# MCB_Output_Connectors.net
KiCad netlist of a schematic drawn in Altium Designer
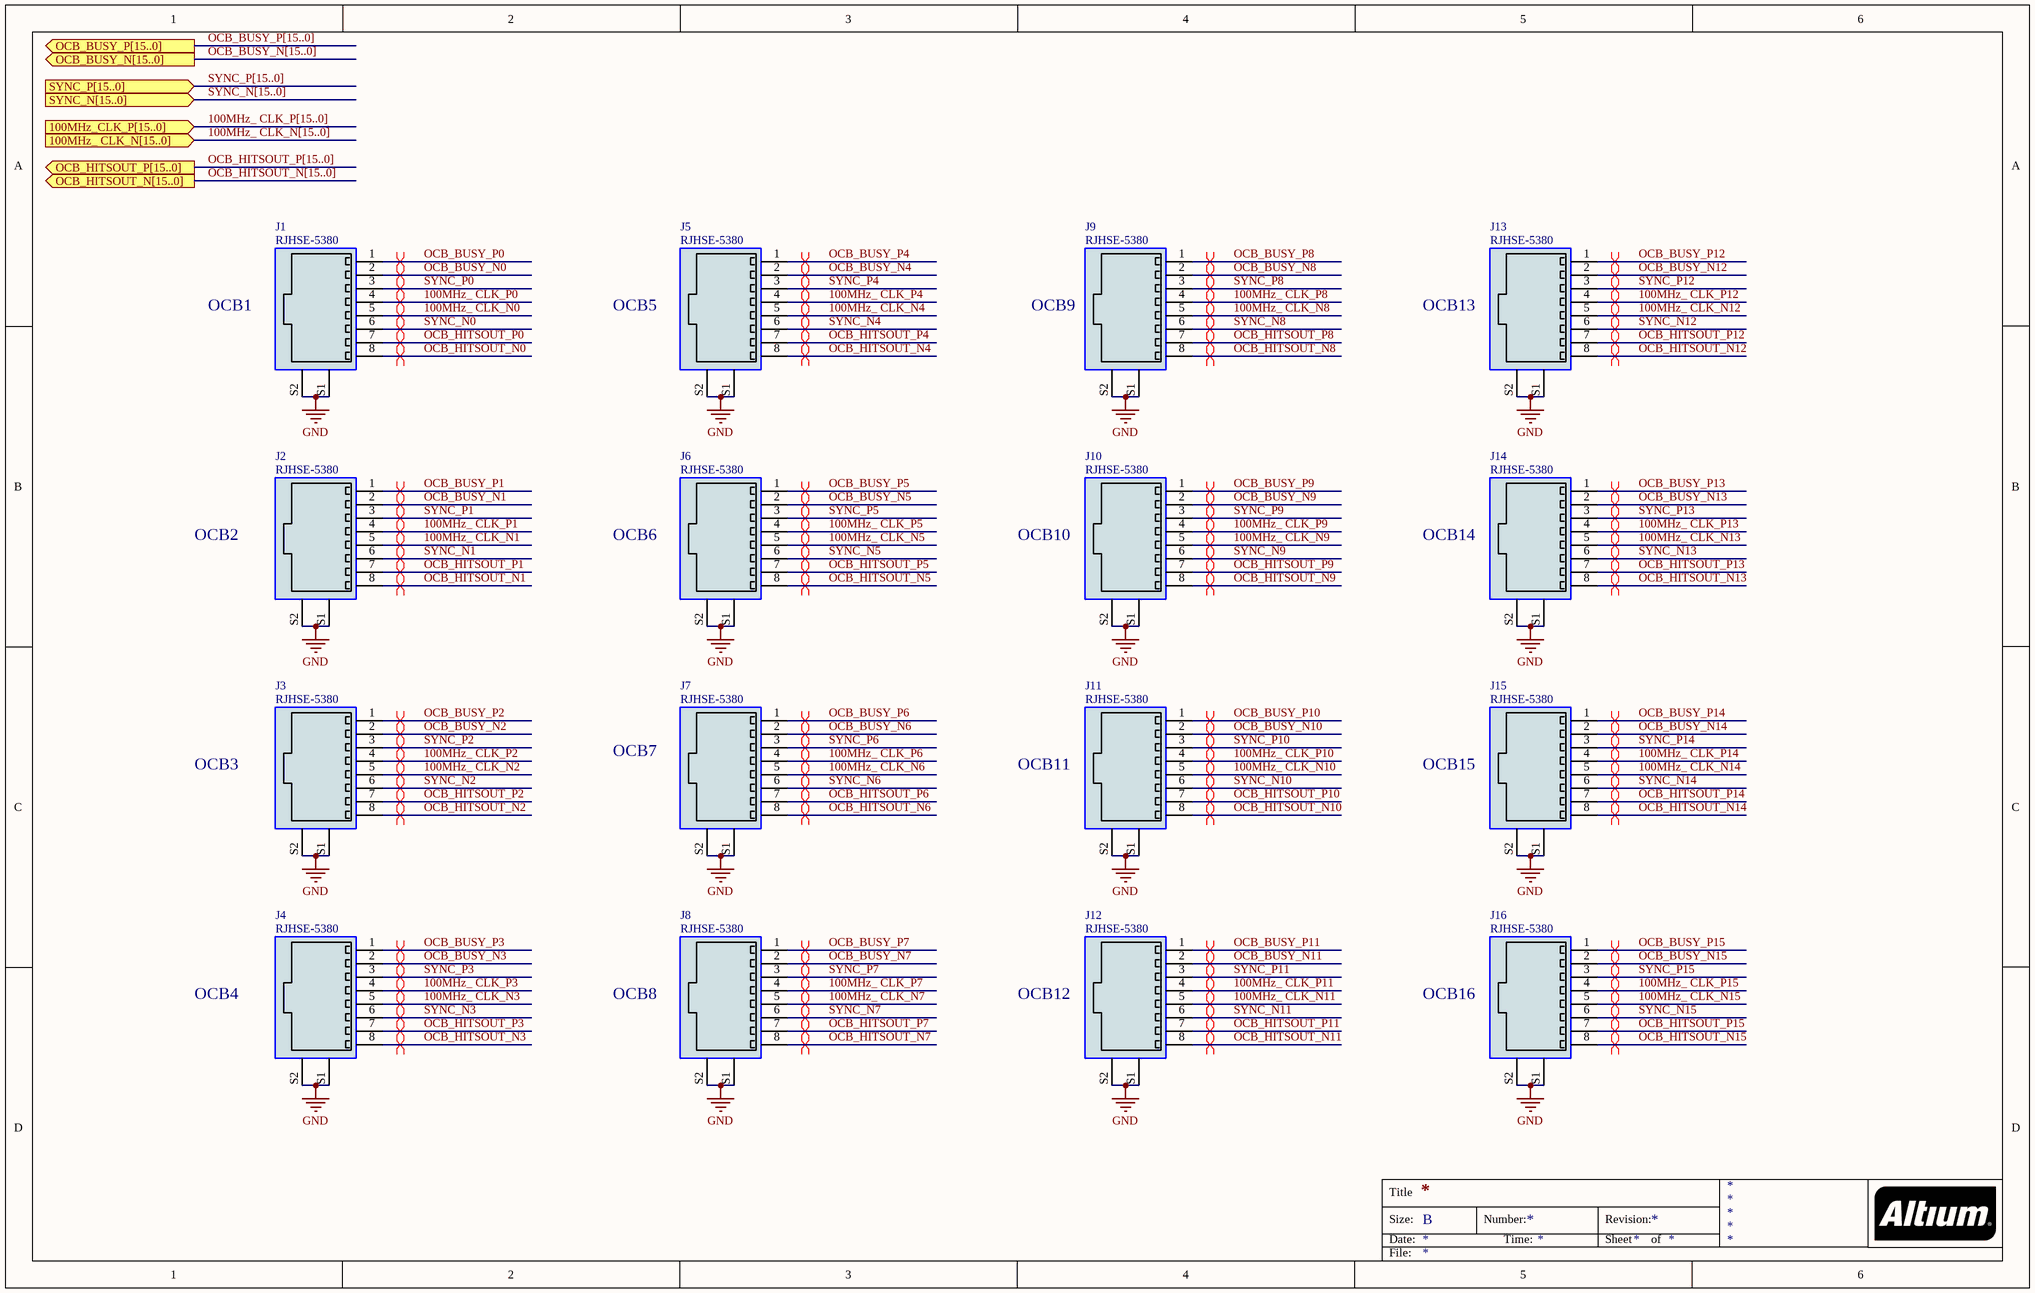
[diagram p0: MCB Output Connectors.SchDoc]

(export (version "E")
  (design (tool "Eeschema 10.0.6"))
  (components
    (comp (ref "J1")
      (value "RJHSE-5380")
      (footprint "RJ45 Right Angle")
      (description "Jack Modular Connector 8p8c (RJ45, Ethernet) 90° Angle (Right) Shielded, EMI Finger -")
      (libsource (lib "MCB") (part "RJHSE-5380"))
    )
    (comp (ref "J2")
      (value "RJHSE-5380")
      (footprint "RJ45 Right Angle")
      (description "Jack Modular Connector 8p8c (RJ45, Ethernet) 90° Angle (Right) Shielded, EMI Finger -")
      (libsource (lib "MCB") (part "RJHSE-5380"))
    )
    (comp (ref "J3")
      (value "RJHSE-5380")
      (footprint "RJ45 Right Angle")
      (description "Jack Modular Connector 8p8c (RJ45, Ethernet) 90° Angle (Right) Shielded, EMI Finger -")
      (libsource (lib "MCB") (part "RJHSE-5380"))
    )
    (comp (ref "J4")
      (value "RJHSE-5380")
      (footprint "RJ45 Right Angle")
      (description "Jack Modular Connector 8p8c (RJ45, Ethernet) 90° Angle (Right) Shielded, EMI Finger -")
      (libsource (lib "MCB") (part "RJHSE-5380"))
    )
    (comp (ref "J5")
      (value "RJHSE-5380")
      (footprint "RJ45 Right Angle")
      (description "Jack Modular Connector 8p8c (RJ45, Ethernet) 90° Angle (Right) Shielded, EMI Finger -")
      (libsource (lib "MCB") (part "RJHSE-5380"))
    )
    (comp (ref "J6")
      (value "RJHSE-5380")
      (footprint "RJ45 Right Angle")
      (description "Jack Modular Connector 8p8c (RJ45, Ethernet) 90° Angle (Right) Shielded, EMI Finger -")
      (libsource (lib "MCB") (part "RJHSE-5380"))
    )
    (comp (ref "J7")
      (value "RJHSE-5380")
      (footprint "RJ45 Right Angle")
      (description "Jack Modular Connector 8p8c (RJ45, Ethernet) 90° Angle (Right) Shielded, EMI Finger -")
      (libsource (lib "MCB") (part "RJHSE-5380"))
    )
    (comp (ref "J8")
      (value "RJHSE-5380")
      (footprint "RJ45 Right Angle")
      (description "Jack Modular Connector 8p8c (RJ45, Ethernet) 90° Angle (Right) Shielded, EMI Finger -")
      (libsource (lib "MCB") (part "RJHSE-5380"))
    )
    (comp (ref "J9")
      (value "RJHSE-5380")
      (footprint "RJ45 Right Angle")
      (description "Jack Modular Connector 8p8c (RJ45, Ethernet) 90° Angle (Right) Shielded, EMI Finger -")
      (libsource (lib "MCB") (part "RJHSE-5380"))
    )
    (comp (ref "J10")
      (value "RJHSE-5380")
      (footprint "RJ45 Right Angle")
      (description "Jack Modular Connector 8p8c (RJ45, Ethernet) 90° Angle (Right) Shielded, EMI Finger -")
      (libsource (lib "MCB") (part "RJHSE-5380"))
    )
    (comp (ref "J11")
      (value "RJHSE-5380")
      (footprint "RJ45 Right Angle")
      (description "Jack Modular Connector 8p8c (RJ45, Ethernet) 90° Angle (Right) Shielded, EMI Finger -")
      (libsource (lib "MCB") (part "RJHSE-5380"))
    )
    (comp (ref "J12")
      (value "RJHSE-5380")
      (footprint "RJ45 Right Angle")
      (description "Jack Modular Connector 8p8c (RJ45, Ethernet) 90° Angle (Right) Shielded, EMI Finger -")
      (libsource (lib "MCB") (part "RJHSE-5380"))
    )
    (comp (ref "J13")
      (value "RJHSE-5380")
      (footprint "RJ45 Right Angle")
      (description "Jack Modular Connector 8p8c (RJ45, Ethernet) 90° Angle (Right) Shielded, EMI Finger -")
      (libsource (lib "MCB") (part "RJHSE-5380"))
    )
    (comp (ref "J14")
      (value "RJHSE-5380")
      (footprint "RJ45 Right Angle")
      (description "Jack Modular Connector 8p8c (RJ45, Ethernet) 90° Angle (Right) Shielded, EMI Finger -")
      (libsource (lib "MCB") (part "RJHSE-5380"))
    )
    (comp (ref "J15")
      (value "RJHSE-5380")
      (footprint "RJ45 Right Angle")
      (description "Jack Modular Connector 8p8c (RJ45, Ethernet) 90° Angle (Right) Shielded, EMI Finger -")
      (libsource (lib "MCB") (part "RJHSE-5380"))
    )
    (comp (ref "J16")
      (value "RJHSE-5380")
      (footprint "RJ45 Right Angle")
      (description "Jack Modular Connector 8p8c (RJ45, Ethernet) 90° Angle (Right) Shielded, EMI Finger -")
      (libsource (lib "MCB") (part "RJHSE-5380"))
    )
  )
  (nets
    (net (code "1") (name "/100MHz_ CLK_N0") (class "Default")
      (node (ref "J1") (pin "5") (pinfunction "5_5") (pintype "passive"))
    )
    (net (code "2") (name "/100MHz_ CLK_N1") (class "Default")
      (node (ref "J2") (pin "5") (pinfunction "5_5") (pintype "passive"))
    )
    (net (code "3") (name "/100MHz_ CLK_N2") (class "Default")
      (node (ref "J3") (pin "5") (pinfunction "5_5") (pintype "passive"))
    )
    (net (code "4") (name "/100MHz_ CLK_N3") (class "Default")
      (node (ref "J4") (pin "5") (pinfunction "5_5") (pintype "passive"))
    )
    (net (code "5") (name "/100MHz_ CLK_N4") (class "Default")
      (node (ref "J5") (pin "5") (pinfunction "5_5") (pintype "passive"))
    )
    (net (code "6") (name "/100MHz_ CLK_N5") (class "Default")
      (node (ref "J6") (pin "5") (pinfunction "5_5") (pintype "passive"))
    )
    (net (code "7") (name "/100MHz_ CLK_N6") (class "Default")
      (node (ref "J7") (pin "5") (pinfunction "5_5") (pintype "passive"))
    )
    (net (code "8") (name "/100MHz_ CLK_N7") (class "Default")
      (node (ref "J8") (pin "5") (pinfunction "5_5") (pintype "passive"))
    )
    (net (code "9") (name "/100MHz_ CLK_N8") (class "Default")
      (node (ref "J9") (pin "5") (pinfunction "5_5") (pintype "passive"))
    )
    (net (code "10") (name "/100MHz_ CLK_N9") (class "Default")
      (node (ref "J10") (pin "5") (pinfunction "5_5") (pintype "passive"))
    )
    (net (code "11") (name "/100MHz_ CLK_N10") (class "Default")
      (node (ref "J11") (pin "5") (pinfunction "5_5") (pintype "passive"))
    )
    (net (code "12") (name "/100MHz_ CLK_N11") (class "Default")
      (node (ref "J12") (pin "5") (pinfunction "5_5") (pintype "passive"))
    )
    (net (code "13") (name "/100MHz_ CLK_N12") (class "Default")
      (node (ref "J13") (pin "5") (pinfunction "5_5") (pintype "passive"))
    )
    (net (code "14") (name "/100MHz_ CLK_N13") (class "Default")
      (node (ref "J14") (pin "5") (pinfunction "5_5") (pintype "passive"))
    )
    (net (code "15") (name "/100MHz_ CLK_N14") (class "Default")
      (node (ref "J15") (pin "5") (pinfunction "5_5") (pintype "passive"))
    )
    (net (code "16") (name "/100MHz_ CLK_N15") (class "Default")
      (node (ref "J16") (pin "5") (pinfunction "5_5") (pintype "passive"))
    )
    (net (code "17") (name "/100MHz_ CLK_P0") (class "Default")
      (node (ref "J1") (pin "4") (pinfunction "4_4") (pintype "passive"))
    )
    (net (code "18") (name "/100MHz_ CLK_P1") (class "Default")
      (node (ref "J2") (pin "4") (pinfunction "4_4") (pintype "passive"))
    )
    (net (code "19") (name "/100MHz_ CLK_P2") (class "Default")
      (node (ref "J3") (pin "4") (pinfunction "4_4") (pintype "passive"))
    )
    (net (code "20") (name "/100MHz_ CLK_P3") (class "Default")
      (node (ref "J4") (pin "4") (pinfunction "4_4") (pintype "passive"))
    )
    (net (code "21") (name "/100MHz_ CLK_P4") (class "Default")
      (node (ref "J5") (pin "4") (pinfunction "4_4") (pintype "passive"))
    )
    (net (code "22") (name "/100MHz_ CLK_P5") (class "Default")
      (node (ref "J6") (pin "4") (pinfunction "4_4") (pintype "passive"))
    )
    (net (code "23") (name "/100MHz_ CLK_P6") (class "Default")
      (node (ref "J7") (pin "4") (pinfunction "4_4") (pintype "passive"))
    )
    (net (code "24") (name "/100MHz_ CLK_P7") (class "Default")
      (node (ref "J8") (pin "4") (pinfunction "4_4") (pintype "passive"))
    )
    (net (code "25") (name "/100MHz_ CLK_P8") (class "Default")
      (node (ref "J9") (pin "4") (pinfunction "4_4") (pintype "passive"))
    )
    (net (code "26") (name "/100MHz_ CLK_P9") (class "Default")
      (node (ref "J10") (pin "4") (pinfunction "4_4") (pintype "passive"))
    )
    (net (code "27") (name "/100MHz_ CLK_P10") (class "Default")
      (node (ref "J11") (pin "4") (pinfunction "4_4") (pintype "passive"))
    )
    (net (code "28") (name "/100MHz_ CLK_P11") (class "Default")
      (node (ref "J12") (pin "4") (pinfunction "4_4") (pintype "passive"))
    )
    (net (code "29") (name "/100MHz_ CLK_P12") (class "Default")
      (node (ref "J13") (pin "4") (pinfunction "4_4") (pintype "passive"))
    )
    (net (code "30") (name "/100MHz_ CLK_P13") (class "Default")
      (node (ref "J14") (pin "4") (pinfunction "4_4") (pintype "passive"))
    )
    (net (code "31") (name "/100MHz_ CLK_P14") (class "Default")
      (node (ref "J15") (pin "4") (pinfunction "4_4") (pintype "passive"))
    )
    (net (code "32") (name "/100MHz_ CLK_P15") (class "Default")
      (node (ref "J16") (pin "4") (pinfunction "4_4") (pintype "passive"))
    )
    (net (code "33") (name "/OCB_BUSY_N0") (class "Default")
      (node (ref "J1") (pin "2") (pinfunction "2_2") (pintype "passive"))
    )
    (net (code "34") (name "/OCB_BUSY_N1") (class "Default")
      (node (ref "J2") (pin "2") (pinfunction "2_2") (pintype "passive"))
    )
    (net (code "35") (name "/OCB_BUSY_N2") (class "Default")
      (node (ref "J3") (pin "2") (pinfunction "2_2") (pintype "passive"))
    )
    (net (code "36") (name "/OCB_BUSY_N3") (class "Default")
      (node (ref "J4") (pin "2") (pinfunction "2_2") (pintype "passive"))
    )
    (net (code "37") (name "/OCB_BUSY_N4") (class "Default")
      (node (ref "J5") (pin "2") (pinfunction "2_2") (pintype "passive"))
    )
    (net (code "38") (name "/OCB_BUSY_N5") (class "Default")
      (node (ref "J6") (pin "2") (pinfunction "2_2") (pintype "passive"))
    )
    (net (code "39") (name "/OCB_BUSY_N6") (class "Default")
      (node (ref "J7") (pin "2") (pinfunction "2_2") (pintype "passive"))
    )
    (net (code "40") (name "/OCB_BUSY_N7") (class "Default")
      (node (ref "J8") (pin "2") (pinfunction "2_2") (pintype "passive"))
    )
    (net (code "41") (name "/OCB_BUSY_N8") (class "Default")
      (node (ref "J9") (pin "2") (pinfunction "2_2") (pintype "passive"))
    )
    (net (code "42") (name "/OCB_BUSY_N9") (class "Default")
      (node (ref "J10") (pin "2") (pinfunction "2_2") (pintype "passive"))
    )
    (net (code "43") (name "/OCB_BUSY_N10") (class "Default")
      (node (ref "J11") (pin "2") (pinfunction "2_2") (pintype "passive"))
    )
    (net (code "44") (name "/OCB_BUSY_N11") (class "Default")
      (node (ref "J12") (pin "2") (pinfunction "2_2") (pintype "passive"))
    )
    (net (code "45") (name "/OCB_BUSY_N12") (class "Default")
      (node (ref "J13") (pin "2") (pinfunction "2_2") (pintype "passive"))
    )
    (net (code "46") (name "/OCB_BUSY_N13") (class "Default")
      (node (ref "J14") (pin "2") (pinfunction "2_2") (pintype "passive"))
    )
    (net (code "47") (name "/OCB_BUSY_N14") (class "Default")
      (node (ref "J15") (pin "2") (pinfunction "2_2") (pintype "passive"))
    )
    (net (code "48") (name "/OCB_BUSY_N15") (class "Default")
      (node (ref "J16") (pin "2") (pinfunction "2_2") (pintype "passive"))
    )
    (net (code "50") (name "/OCB_BUSY_P0") (class "Default")
      (node (ref "J1") (pin "1") (pinfunction "1_1") (pintype "passive"))
    )
    (net (code "51") (name "/OCB_BUSY_P1") (class "Default")
      (node (ref "J2") (pin "1") (pinfunction "1_1") (pintype "passive"))
    )
    (net (code "52") (name "/OCB_BUSY_P2") (class "Default")
      (node (ref "J3") (pin "1") (pinfunction "1_1") (pintype "passive"))
    )
    (net (code "53") (name "/OCB_BUSY_P3") (class "Default")
      (node (ref "J4") (pin "1") (pinfunction "1_1") (pintype "passive"))
    )
    (net (code "54") (name "/OCB_BUSY_P4") (class "Default")
      (node (ref "J5") (pin "1") (pinfunction "1_1") (pintype "passive"))
    )
    (net (code "55") (name "/OCB_BUSY_P5") (class "Default")
      (node (ref "J6") (pin "1") (pinfunction "1_1") (pintype "passive"))
    )
    (net (code "56") (name "/OCB_BUSY_P6") (class "Default")
      (node (ref "J7") (pin "1") (pinfunction "1_1") (pintype "passive"))
    )
    (net (code "57") (name "/OCB_BUSY_P7") (class "Default")
      (node (ref "J8") (pin "1") (pinfunction "1_1") (pintype "passive"))
    )
    (net (code "58") (name "/OCB_BUSY_P8") (class "Default")
      (node (ref "J9") (pin "1") (pinfunction "1_1") (pintype "passive"))
    )
    (net (code "59") (name "/OCB_BUSY_P9") (class "Default")
      (node (ref "J10") (pin "1") (pinfunction "1_1") (pintype "passive"))
    )
    (net (code "60") (name "/OCB_BUSY_P10") (class "Default")
      (node (ref "J11") (pin "1") (pinfunction "1_1") (pintype "passive"))
    )
    (net (code "61") (name "/OCB_BUSY_P11") (class "Default")
      (node (ref "J12") (pin "1") (pinfunction "1_1") (pintype "passive"))
    )
    (net (code "62") (name "/OCB_BUSY_P12") (class "Default")
      (node (ref "J13") (pin "1") (pinfunction "1_1") (pintype "passive"))
    )
    (net (code "63") (name "/OCB_BUSY_P13") (class "Default")
      (node (ref "J14") (pin "1") (pinfunction "1_1") (pintype "passive"))
    )
    (net (code "64") (name "/OCB_BUSY_P14") (class "Default")
      (node (ref "J15") (pin "1") (pinfunction "1_1") (pintype "passive"))
    )
    (net (code "65") (name "/OCB_BUSY_P15") (class "Default")
      (node (ref "J16") (pin "1") (pinfunction "1_1") (pintype "passive"))
    )
    (net (code "67") (name "/OCB_HITSOUT_N0") (class "Default")
      (node (ref "J1") (pin "8") (pinfunction "8_8") (pintype "passive"))
    )
    (net (code "68") (name "/OCB_HITSOUT_N1") (class "Default")
      (node (ref "J2") (pin "8") (pinfunction "8_8") (pintype "passive"))
    )
    (net (code "69") (name "/OCB_HITSOUT_N2") (class "Default")
      (node (ref "J3") (pin "8") (pinfunction "8_8") (pintype "passive"))
    )
    (net (code "70") (name "/OCB_HITSOUT_N3") (class "Default")
      (node (ref "J4") (pin "8") (pinfunction "8_8") (pintype "passive"))
    )
    (net (code "71") (name "/OCB_HITSOUT_N4") (class "Default")
      (node (ref "J5") (pin "8") (pinfunction "8_8") (pintype "passive"))
    )
    (net (code "72") (name "/OCB_HITSOUT_N5") (class "Default")
      (node (ref "J6") (pin "8") (pinfunction "8_8") (pintype "passive"))
    )
    (net (code "73") (name "/OCB_HITSOUT_N6") (class "Default")
      (node (ref "J7") (pin "8") (pinfunction "8_8") (pintype "passive"))
    )
    (net (code "74") (name "/OCB_HITSOUT_N7") (class "Default")
      (node (ref "J8") (pin "8") (pinfunction "8_8") (pintype "passive"))
    )
    (net (code "75") (name "/OCB_HITSOUT_N8") (class "Default")
      (node (ref "J9") (pin "8") (pinfunction "8_8") (pintype "passive"))
    )
    (net (code "76") (name "/OCB_HITSOUT_N9") (class "Default")
      (node (ref "J10") (pin "8") (pinfunction "8_8") (pintype "passive"))
    )
    (net (code "77") (name "/OCB_HITSOUT_N10") (class "Default")
      (node (ref "J11") (pin "8") (pinfunction "8_8") (pintype "passive"))
    )
    (net (code "78") (name "/OCB_HITSOUT_N11") (class "Default")
      (node (ref "J12") (pin "8") (pinfunction "8_8") (pintype "passive"))
    )
    (net (code "79") (name "/OCB_HITSOUT_N12") (class "Default")
      (node (ref "J13") (pin "8") (pinfunction "8_8") (pintype "passive"))
    )
    (net (code "80") (name "/OCB_HITSOUT_N13") (class "Default")
      (node (ref "J14") (pin "8") (pinfunction "8_8") (pintype "passive"))
    )
    (net (code "81") (name "/OCB_HITSOUT_N14") (class "Default")
      (node (ref "J15") (pin "8") (pinfunction "8_8") (pintype "passive"))
    )
    (net (code "82") (name "/OCB_HITSOUT_N15") (class "Default")
      (node (ref "J16") (pin "8") (pinfunction "8_8") (pintype "passive"))
    )
    (net (code "84") (name "/OCB_HITSOUT_P0") (class "Default")
      (node (ref "J1") (pin "7") (pinfunction "7_7") (pintype "passive"))
    )
    (net (code "85") (name "/OCB_HITSOUT_P1") (class "Default")
      (node (ref "J2") (pin "7") (pinfunction "7_7") (pintype "passive"))
    )
    (net (code "86") (name "/OCB_HITSOUT_P2") (class "Default")
      (node (ref "J3") (pin "7") (pinfunction "7_7") (pintype "passive"))
    )
    (net (code "87") (name "/OCB_HITSOUT_P3") (class "Default")
      (node (ref "J4") (pin "7") (pinfunction "7_7") (pintype "passive"))
    )
    (net (code "88") (name "/OCB_HITSOUT_P4") (class "Default")
      (node (ref "J5") (pin "7") (pinfunction "7_7") (pintype "passive"))
    )
    (net (code "89") (name "/OCB_HITSOUT_P5") (class "Default")
      (node (ref "J6") (pin "7") (pinfunction "7_7") (pintype "passive"))
    )
    (net (code "90") (name "/OCB_HITSOUT_P6") (class "Default")
      (node (ref "J7") (pin "7") (pinfunction "7_7") (pintype "passive"))
    )
    (net (code "91") (name "/OCB_HITSOUT_P7") (class "Default")
      (node (ref "J8") (pin "7") (pinfunction "7_7") (pintype "passive"))
    )
    (net (code "92") (name "/OCB_HITSOUT_P8") (class "Default")
      (node (ref "J9") (pin "7") (pinfunction "7_7") (pintype "passive"))
    )
    (net (code "93") (name "/OCB_HITSOUT_P9") (class "Default")
      (node (ref "J10") (pin "7") (pinfunction "7_7") (pintype "passive"))
    )
    (net (code "94") (name "/OCB_HITSOUT_P10") (class "Default")
      (node (ref "J11") (pin "7") (pinfunction "7_7") (pintype "passive"))
    )
    (net (code "95") (name "/OCB_HITSOUT_P11") (class "Default")
      (node (ref "J12") (pin "7") (pinfunction "7_7") (pintype "passive"))
    )
    (net (code "96") (name "/OCB_HITSOUT_P12") (class "Default")
      (node (ref "J13") (pin "7") (pinfunction "7_7") (pintype "passive"))
    )
    (net (code "97") (name "/OCB_HITSOUT_P13") (class "Default")
      (node (ref "J14") (pin "7") (pinfunction "7_7") (pintype "passive"))
    )
    (net (code "98") (name "/OCB_HITSOUT_P14") (class "Default")
      (node (ref "J15") (pin "7") (pinfunction "7_7") (pintype "passive"))
    )
    (net (code "99") (name "/OCB_HITSOUT_P15") (class "Default")
      (node (ref "J16") (pin "7") (pinfunction "7_7") (pintype "passive"))
    )
    (net (code "101") (name "/SYNC_N0") (class "Default")
      (node (ref "J1") (pin "6") (pinfunction "6_6") (pintype "passive"))
    )
    (net (code "102") (name "/SYNC_N1") (class "Default")
      (node (ref "J2") (pin "6") (pinfunction "6_6") (pintype "passive"))
    )
    (net (code "103") (name "/SYNC_N2") (class "Default")
      (node (ref "J3") (pin "6") (pinfunction "6_6") (pintype "passive"))
    )
    (net (code "104") (name "/SYNC_N3") (class "Default")
      (node (ref "J4") (pin "6") (pinfunction "6_6") (pintype "passive"))
    )
    (net (code "105") (name "/SYNC_N4") (class "Default")
      (node (ref "J5") (pin "6") (pinfunction "6_6") (pintype "passive"))
    )
    (net (code "106") (name "/SYNC_N5") (class "Default")
      (node (ref "J6") (pin "6") (pinfunction "6_6") (pintype "passive"))
    )
    (net (code "107") (name "/SYNC_N6") (class "Default")
      (node (ref "J7") (pin "6") (pinfunction "6_6") (pintype "passive"))
    )
    (net (code "108") (name "/SYNC_N7") (class "Default")
      (node (ref "J8") (pin "6") (pinfunction "6_6") (pintype "passive"))
    )
    (net (code "109") (name "/SYNC_N8") (class "Default")
      (node (ref "J9") (pin "6") (pinfunction "6_6") (pintype "passive"))
    )
    (net (code "110") (name "/SYNC_N9") (class "Default")
      (node (ref "J10") (pin "6") (pinfunction "6_6") (pintype "passive"))
    )
    (net (code "111") (name "/SYNC_N10") (class "Default")
      (node (ref "J11") (pin "6") (pinfunction "6_6") (pintype "passive"))
    )
    (net (code "112") (name "/SYNC_N11") (class "Default")
      (node (ref "J12") (pin "6") (pinfunction "6_6") (pintype "passive"))
    )
    (net (code "113") (name "/SYNC_N12") (class "Default")
      (node (ref "J13") (pin "6") (pinfunction "6_6") (pintype "passive"))
    )
    (net (code "114") (name "/SYNC_N13") (class "Default")
      (node (ref "J14") (pin "6") (pinfunction "6_6") (pintype "passive"))
    )
    (net (code "115") (name "/SYNC_N14") (class "Default")
      (node (ref "J15") (pin "6") (pinfunction "6_6") (pintype "passive"))
    )
    (net (code "116") (name "/SYNC_N15") (class "Default")
      (node (ref "J16") (pin "6") (pinfunction "6_6") (pintype "passive"))
    )
    (net (code "118") (name "/SYNC_P0") (class "Default")
      (node (ref "J1") (pin "3") (pinfunction "3_3") (pintype "passive"))
    )
    (net (code "119") (name "/SYNC_P1") (class "Default")
      (node (ref "J2") (pin "3") (pinfunction "3_3") (pintype "passive"))
    )
    (net (code "120") (name "/SYNC_P2") (class "Default")
      (node (ref "J3") (pin "3") (pinfunction "3_3") (pintype "passive"))
    )
    (net (code "121") (name "/SYNC_P3") (class "Default")
      (node (ref "J4") (pin "3") (pinfunction "3_3") (pintype "passive"))
    )
    (net (code "122") (name "/SYNC_P4") (class "Default")
      (node (ref "J5") (pin "3") (pinfunction "3_3") (pintype "passive"))
    )
    (net (code "123") (name "/SYNC_P5") (class "Default")
      (node (ref "J6") (pin "3") (pinfunction "3_3") (pintype "passive"))
    )
    (net (code "124") (name "/SYNC_P6") (class "Default")
      (node (ref "J7") (pin "3") (pinfunction "3_3") (pintype "passive"))
    )
    (net (code "125") (name "/SYNC_P7") (class "Default")
      (node (ref "J8") (pin "3") (pinfunction "3_3") (pintype "passive"))
    )
    (net (code "126") (name "/SYNC_P8") (class "Default")
      (node (ref "J9") (pin "3") (pinfunction "3_3") (pintype "passive"))
    )
    (net (code "127") (name "/SYNC_P9") (class "Default")
      (node (ref "J10") (pin "3") (pinfunction "3_3") (pintype "passive"))
    )
    (net (code "128") (name "/SYNC_P10") (class "Default")
      (node (ref "J11") (pin "3") (pinfunction "3_3") (pintype "passive"))
    )
    (net (code "129") (name "/SYNC_P11") (class "Default")
      (node (ref "J12") (pin "3") (pinfunction "3_3") (pintype "passive"))
    )
    (net (code "130") (name "/SYNC_P12") (class "Default")
      (node (ref "J13") (pin "3") (pinfunction "3_3") (pintype "passive"))
    )
    (net (code "131") (name "/SYNC_P13") (class "Default")
      (node (ref "J14") (pin "3") (pinfunction "3_3") (pintype "passive"))
    )
    (net (code "132") (name "/SYNC_P14") (class "Default")
      (node (ref "J15") (pin "3") (pinfunction "3_3") (pintype "passive"))
    )
    (net (code "133") (name "/SYNC_P15") (class "Default")
      (node (ref "J16") (pin "3") (pinfunction "3_3") (pintype "passive"))
    )
    (net (code "137") (name "GND") (class "Default")
      (node (ref "J1") (pin "S1") (pinfunction "SHIELD_S1") (pintype "passive"))
      (node (ref "J1") (pin "S2") (pinfunction "SHIELD_S2") (pintype "passive"))
      (node (ref "J10") (pin "S1") (pinfunction "SHIELD_S1") (pintype "passive"))
      (node (ref "J10") (pin "S2") (pinfunction "SHIELD_S2") (pintype "passive"))
      (node (ref "J11") (pin "S1") (pinfunction "SHIELD_S1") (pintype "passive"))
      (node (ref "J11") (pin "S2") (pinfunction "SHIELD_S2") (pintype "passive"))
      (node (ref "J12") (pin "S1") (pinfunction "SHIELD_S1") (pintype "passive"))
      (node (ref "J12") (pin "S2") (pinfunction "SHIELD_S2") (pintype "passive"))
      (node (ref "J13") (pin "S1") (pinfunction "SHIELD_S1") (pintype "passive"))
      (node (ref "J13") (pin "S2") (pinfunction "SHIELD_S2") (pintype "passive"))
      (node (ref "J14") (pin "S1") (pinfunction "SHIELD_S1") (pintype "passive"))
      (node (ref "J14") (pin "S2") (pinfunction "SHIELD_S2") (pintype "passive"))
      (node (ref "J15") (pin "S1") (pinfunction "SHIELD_S1") (pintype "passive"))
      (node (ref "J15") (pin "S2") (pinfunction "SHIELD_S2") (pintype "passive"))
      (node (ref "J16") (pin "S1") (pinfunction "SHIELD_S1") (pintype "passive"))
      (node (ref "J16") (pin "S2") (pinfunction "SHIELD_S2") (pintype "passive"))
      (node (ref "J2") (pin "S1") (pinfunction "SHIELD_S1") (pintype "passive"))
      (node (ref "J2") (pin "S2") (pinfunction "SHIELD_S2") (pintype "passive"))
      (node (ref "J3") (pin "S1") (pinfunction "SHIELD_S1") (pintype "passive"))
      (node (ref "J3") (pin "S2") (pinfunction "SHIELD_S2") (pintype "passive"))
      (node (ref "J4") (pin "S1") (pinfunction "SHIELD_S1") (pintype "passive"))
      (node (ref "J4") (pin "S2") (pinfunction "SHIELD_S2") (pintype "passive"))
      (node (ref "J5") (pin "S1") (pinfunction "SHIELD_S1") (pintype "passive"))
      (node (ref "J5") (pin "S2") (pinfunction "SHIELD_S2") (pintype "passive"))
      (node (ref "J6") (pin "S1") (pinfunction "SHIELD_S1") (pintype "passive"))
      (node (ref "J6") (pin "S2") (pinfunction "SHIELD_S2") (pintype "passive"))
      (node (ref "J7") (pin "S1") (pinfunction "SHIELD_S1") (pintype "passive"))
      (node (ref "J7") (pin "S2") (pinfunction "SHIELD_S2") (pintype "passive"))
      (node (ref "J8") (pin "S1") (pinfunction "SHIELD_S1") (pintype "passive"))
      (node (ref "J8") (pin "S2") (pinfunction "SHIELD_S2") (pintype "passive"))
      (node (ref "J9") (pin "S1") (pinfunction "SHIELD_S1") (pintype "passive"))
      (node (ref "J9") (pin "S2") (pinfunction "SHIELD_S2") (pintype "passive"))
    )
    (net (code "138") (name "unconnected-(J1-Pad9)") (class "Default")
      (node (ref "J1") (pin "9") (pinfunction "9_9") (pintype "passive"))
    )
    (net (code "139") (name "unconnected-(J1-Pad10)") (class "Default")
      (node (ref "J1") (pin "10") (pinfunction "10_10") (pintype "passive"))
    )
    (net (code "140") (name "unconnected-(J1-Pad11)") (class "Default")
      (node (ref "J1") (pin "11") (pinfunction "11_11") (pintype "passive"))
    )
    (net (code "141") (name "unconnected-(J1-Pad12)") (class "Default")
      (node (ref "J1") (pin "12") (pinfunction "12_12") (pintype "passive"))
    )
    (net (code "142") (name "unconnected-(J2-Pad9)") (class "Default")
      (node (ref "J2") (pin "9") (pinfunction "9_9") (pintype "passive"))
    )
    (net (code "143") (name "unconnected-(J2-Pad10)") (class "Default")
      (node (ref "J2") (pin "10") (pinfunction "10_10") (pintype "passive"))
    )
    (net (code "144") (name "unconnected-(J2-Pad11)") (class "Default")
      (node (ref "J2") (pin "11") (pinfunction "11_11") (pintype "passive"))
    )
    (net (code "145") (name "unconnected-(J2-Pad12)") (class "Default")
      (node (ref "J2") (pin "12") (pinfunction "12_12") (pintype "passive"))
    )
    (net (code "146") (name "unconnected-(J3-Pad9)") (class "Default")
      (node (ref "J3") (pin "9") (pinfunction "9_9") (pintype "passive"))
    )
    (net (code "147") (name "unconnected-(J3-Pad10)") (class "Default")
      (node (ref "J3") (pin "10") (pinfunction "10_10") (pintype "passive"))
    )
    (net (code "148") (name "unconnected-(J3-Pad11)") (class "Default")
      (node (ref "J3") (pin "11") (pinfunction "11_11") (pintype "passive"))
    )
    (net (code "149") (name "unconnected-(J3-Pad12)") (class "Default")
      (node (ref "J3") (pin "12") (pinfunction "12_12") (pintype "passive"))
    )
    (net (code "150") (name "unconnected-(J4-Pad9)") (class "Default")
      (node (ref "J4") (pin "9") (pinfunction "9_9") (pintype "passive"))
    )
    (net (code "151") (name "unconnected-(J4-Pad10)") (class "Default")
      (node (ref "J4") (pin "10") (pinfunction "10_10") (pintype "passive"))
    )
    (net (code "152") (name "unconnected-(J4-Pad11)") (class "Default")
      (node (ref "J4") (pin "11") (pinfunction "11_11") (pintype "passive"))
    )
    (net (code "153") (name "unconnected-(J4-Pad12)") (class "Default")
      (node (ref "J4") (pin "12") (pinfunction "12_12") (pintype "passive"))
    )
    (net (code "154") (name "unconnected-(J5-Pad9)") (class "Default")
      (node (ref "J5") (pin "9") (pinfunction "9_9") (pintype "passive"))
    )
    (net (code "155") (name "unconnected-(J5-Pad10)") (class "Default")
      (node (ref "J5") (pin "10") (pinfunction "10_10") (pintype "passive"))
    )
    (net (code "156") (name "unconnected-(J5-Pad11)") (class "Default")
      (node (ref "J5") (pin "11") (pinfunction "11_11") (pintype "passive"))
    )
    (net (code "157") (name "unconnected-(J5-Pad12)") (class "Default")
      (node (ref "J5") (pin "12") (pinfunction "12_12") (pintype "passive"))
    )
    (net (code "158") (name "unconnected-(J6-Pad9)") (class "Default")
      (node (ref "J6") (pin "9") (pinfunction "9_9") (pintype "passive"))
    )
    (net (code "159") (name "unconnected-(J6-Pad10)") (class "Default")
      (node (ref "J6") (pin "10") (pinfunction "10_10") (pintype "passive"))
    )
    (net (code "160") (name "unconnected-(J6-Pad11)") (class "Default")
      (node (ref "J6") (pin "11") (pinfunction "11_11") (pintype "passive"))
    )
    (net (code "161") (name "unconnected-(J6-Pad12)") (class "Default")
      (node (ref "J6") (pin "12") (pinfunction "12_12") (pintype "passive"))
    )
    (net (code "162") (name "unconnected-(J7-Pad9)") (class "Default")
      (node (ref "J7") (pin "9") (pinfunction "9_9") (pintype "passive"))
    )
    (net (code "163") (name "unconnected-(J7-Pad10)") (class "Default")
      (node (ref "J7") (pin "10") (pinfunction "10_10") (pintype "passive"))
    )
    (net (code "164") (name "unconnected-(J7-Pad11)") (class "Default")
      (node (ref "J7") (pin "11") (pinfunction "11_11") (pintype "passive"))
    )
    (net (code "165") (name "unconnected-(J7-Pad12)") (class "Default")
      (node (ref "J7") (pin "12") (pinfunction "12_12") (pintype "passive"))
    )
    (net (code "166") (name "unconnected-(J8-Pad9)") (class "Default")
      (node (ref "J8") (pin "9") (pinfunction "9_9") (pintype "passive"))
    )
    (net (code "167") (name "unconnected-(J8-Pad10)") (class "Default")
      (node (ref "J8") (pin "10") (pinfunction "10_10") (pintype "passive"))
    )
    (net (code "168") (name "unconnected-(J8-Pad11)") (class "Default")
      (node (ref "J8") (pin "11") (pinfunction "11_11") (pintype "passive"))
    )
    (net (code "169") (name "unconnected-(J8-Pad12)") (class "Default")
      (node (ref "J8") (pin "12") (pinfunction "12_12") (pintype "passive"))
    )
    (net (code "170") (name "unconnected-(J9-Pad9)") (class "Default")
      (node (ref "J9") (pin "9") (pinfunction "9_9") (pintype "passive"))
    )
    (net (code "171") (name "unconnected-(J9-Pad10)") (class "Default")
      (node (ref "J9") (pin "10") (pinfunction "10_10") (pintype "passive"))
    )
    (net (code "172") (name "unconnected-(J9-Pad11)") (class "Default")
      (node (ref "J9") (pin "11") (pinfunction "11_11") (pintype "passive"))
    )
    (net (code "173") (name "unconnected-(J9-Pad12)") (class "Default")
      (node (ref "J9") (pin "12") (pinfunction "12_12") (pintype "passive"))
    )
    (net (code "174") (name "unconnected-(J10-Pad9)") (class "Default")
      (node (ref "J10") (pin "9") (pinfunction "9_9") (pintype "passive"))
    )
    (net (code "175") (name "unconnected-(J10-Pad10)") (class "Default")
      (node (ref "J10") (pin "10") (pinfunction "10_10") (pintype "passive"))
    )
    (net (code "176") (name "unconnected-(J10-Pad11)") (class "Default")
      (node (ref "J10") (pin "11") (pinfunction "11_11") (pintype "passive"))
    )
    (net (code "177") (name "unconnected-(J10-Pad12)") (class "Default")
      (node (ref "J10") (pin "12") (pinfunction "12_12") (pintype "passive"))
    )
    (net (code "178") (name "unconnected-(J11-Pad9)") (class "Default")
      (node (ref "J11") (pin "9") (pinfunction "9_9") (pintype "passive"))
    )
    (net (code "179") (name "unconnected-(J11-Pad10)") (class "Default")
      (node (ref "J11") (pin "10") (pinfunction "10_10") (pintype "passive"))
    )
    (net (code "180") (name "unconnected-(J11-Pad11)") (class "Default")
      (node (ref "J11") (pin "11") (pinfunction "11_11") (pintype "passive"))
    )
    (net (code "181") (name "unconnected-(J11-Pad12)") (class "Default")
      (node (ref "J11") (pin "12") (pinfunction "12_12") (pintype "passive"))
    )
    (net (code "182") (name "unconnected-(J12-Pad9)") (class "Default")
      (node (ref "J12") (pin "9") (pinfunction "9_9") (pintype "passive"))
    )
    (net (code "183") (name "unconnected-(J12-Pad10)") (class "Default")
      (node (ref "J12") (pin "10") (pinfunction "10_10") (pintype "passive"))
    )
    (net (code "184") (name "unconnected-(J12-Pad11)") (class "Default")
      (node (ref "J12") (pin "11") (pinfunction "11_11") (pintype "passive"))
    )
    (net (code "185") (name "unconnected-(J12-Pad12)") (class "Default")
      (node (ref "J12") (pin "12") (pinfunction "12_12") (pintype "passive"))
    )
    (net (code "186") (name "unconnected-(J13-Pad9)") (class "Default")
      (node (ref "J13") (pin "9") (pinfunction "9_9") (pintype "passive"))
    )
    (net (code "187") (name "unconnected-(J13-Pad10)") (class "Default")
      (node (ref "J13") (pin "10") (pinfunction "10_10") (pintype "passive"))
    )
    (net (code "188") (name "unconnected-(J13-Pad11)") (class "Default")
      (node (ref "J13") (pin "11") (pinfunction "11_11") (pintype "passive"))
    )
    (net (code "189") (name "unconnected-(J13-Pad12)") (class "Default")
      (node (ref "J13") (pin "12") (pinfunction "12_12") (pintype "passive"))
    )
    (net (code "190") (name "unconnected-(J14-Pad9)") (class "Default")
      (node (ref "J14") (pin "9") (pinfunction "9_9") (pintype "passive"))
    )
    (net (code "191") (name "unconnected-(J14-Pad10)") (class "Default")
      (node (ref "J14") (pin "10") (pinfunction "10_10") (pintype "passive"))
    )
    (net (code "192") (name "unconnected-(J14-Pad11)") (class "Default")
      (node (ref "J14") (pin "11") (pinfunction "11_11") (pintype "passive"))
    )
    (net (code "193") (name "unconnected-(J14-Pad12)") (class "Default")
      (node (ref "J14") (pin "12") (pinfunction "12_12") (pintype "passive"))
    )
    (net (code "194") (name "unconnected-(J15-Pad9)") (class "Default")
      (node (ref "J15") (pin "9") (pinfunction "9_9") (pintype "passive"))
    )
    (net (code "195") (name "unconnected-(J15-Pad10)") (class "Default")
      (node (ref "J15") (pin "10") (pinfunction "10_10") (pintype "passive"))
    )
    (net (code "196") (name "unconnected-(J15-Pad11)") (class "Default")
      (node (ref "J15") (pin "11") (pinfunction "11_11") (pintype "passive"))
    )
    (net (code "197") (name "unconnected-(J15-Pad12)") (class "Default")
      (node (ref "J15") (pin "12") (pinfunction "12_12") (pintype "passive"))
    )
    (net (code "198") (name "unconnected-(J16-Pad9)") (class "Default")
      (node (ref "J16") (pin "9") (pinfunction "9_9") (pintype "passive"))
    )
    (net (code "199") (name "unconnected-(J16-Pad10)") (class "Default")
      (node (ref "J16") (pin "10") (pinfunction "10_10") (pintype "passive"))
    )
    (net (code "200") (name "unconnected-(J16-Pad11)") (class "Default")
      (node (ref "J16") (pin "11") (pinfunction "11_11") (pintype "passive"))
    )
    (net (code "201") (name "unconnected-(J16-Pad12)") (class "Default")
      (node (ref "J16") (pin "12") (pinfunction "12_12") (pintype "passive"))
    )
  )
)
